# JacdacNRF52833HighPower_32.net
KiCad netlist of a schematic drawn in Altium Designer
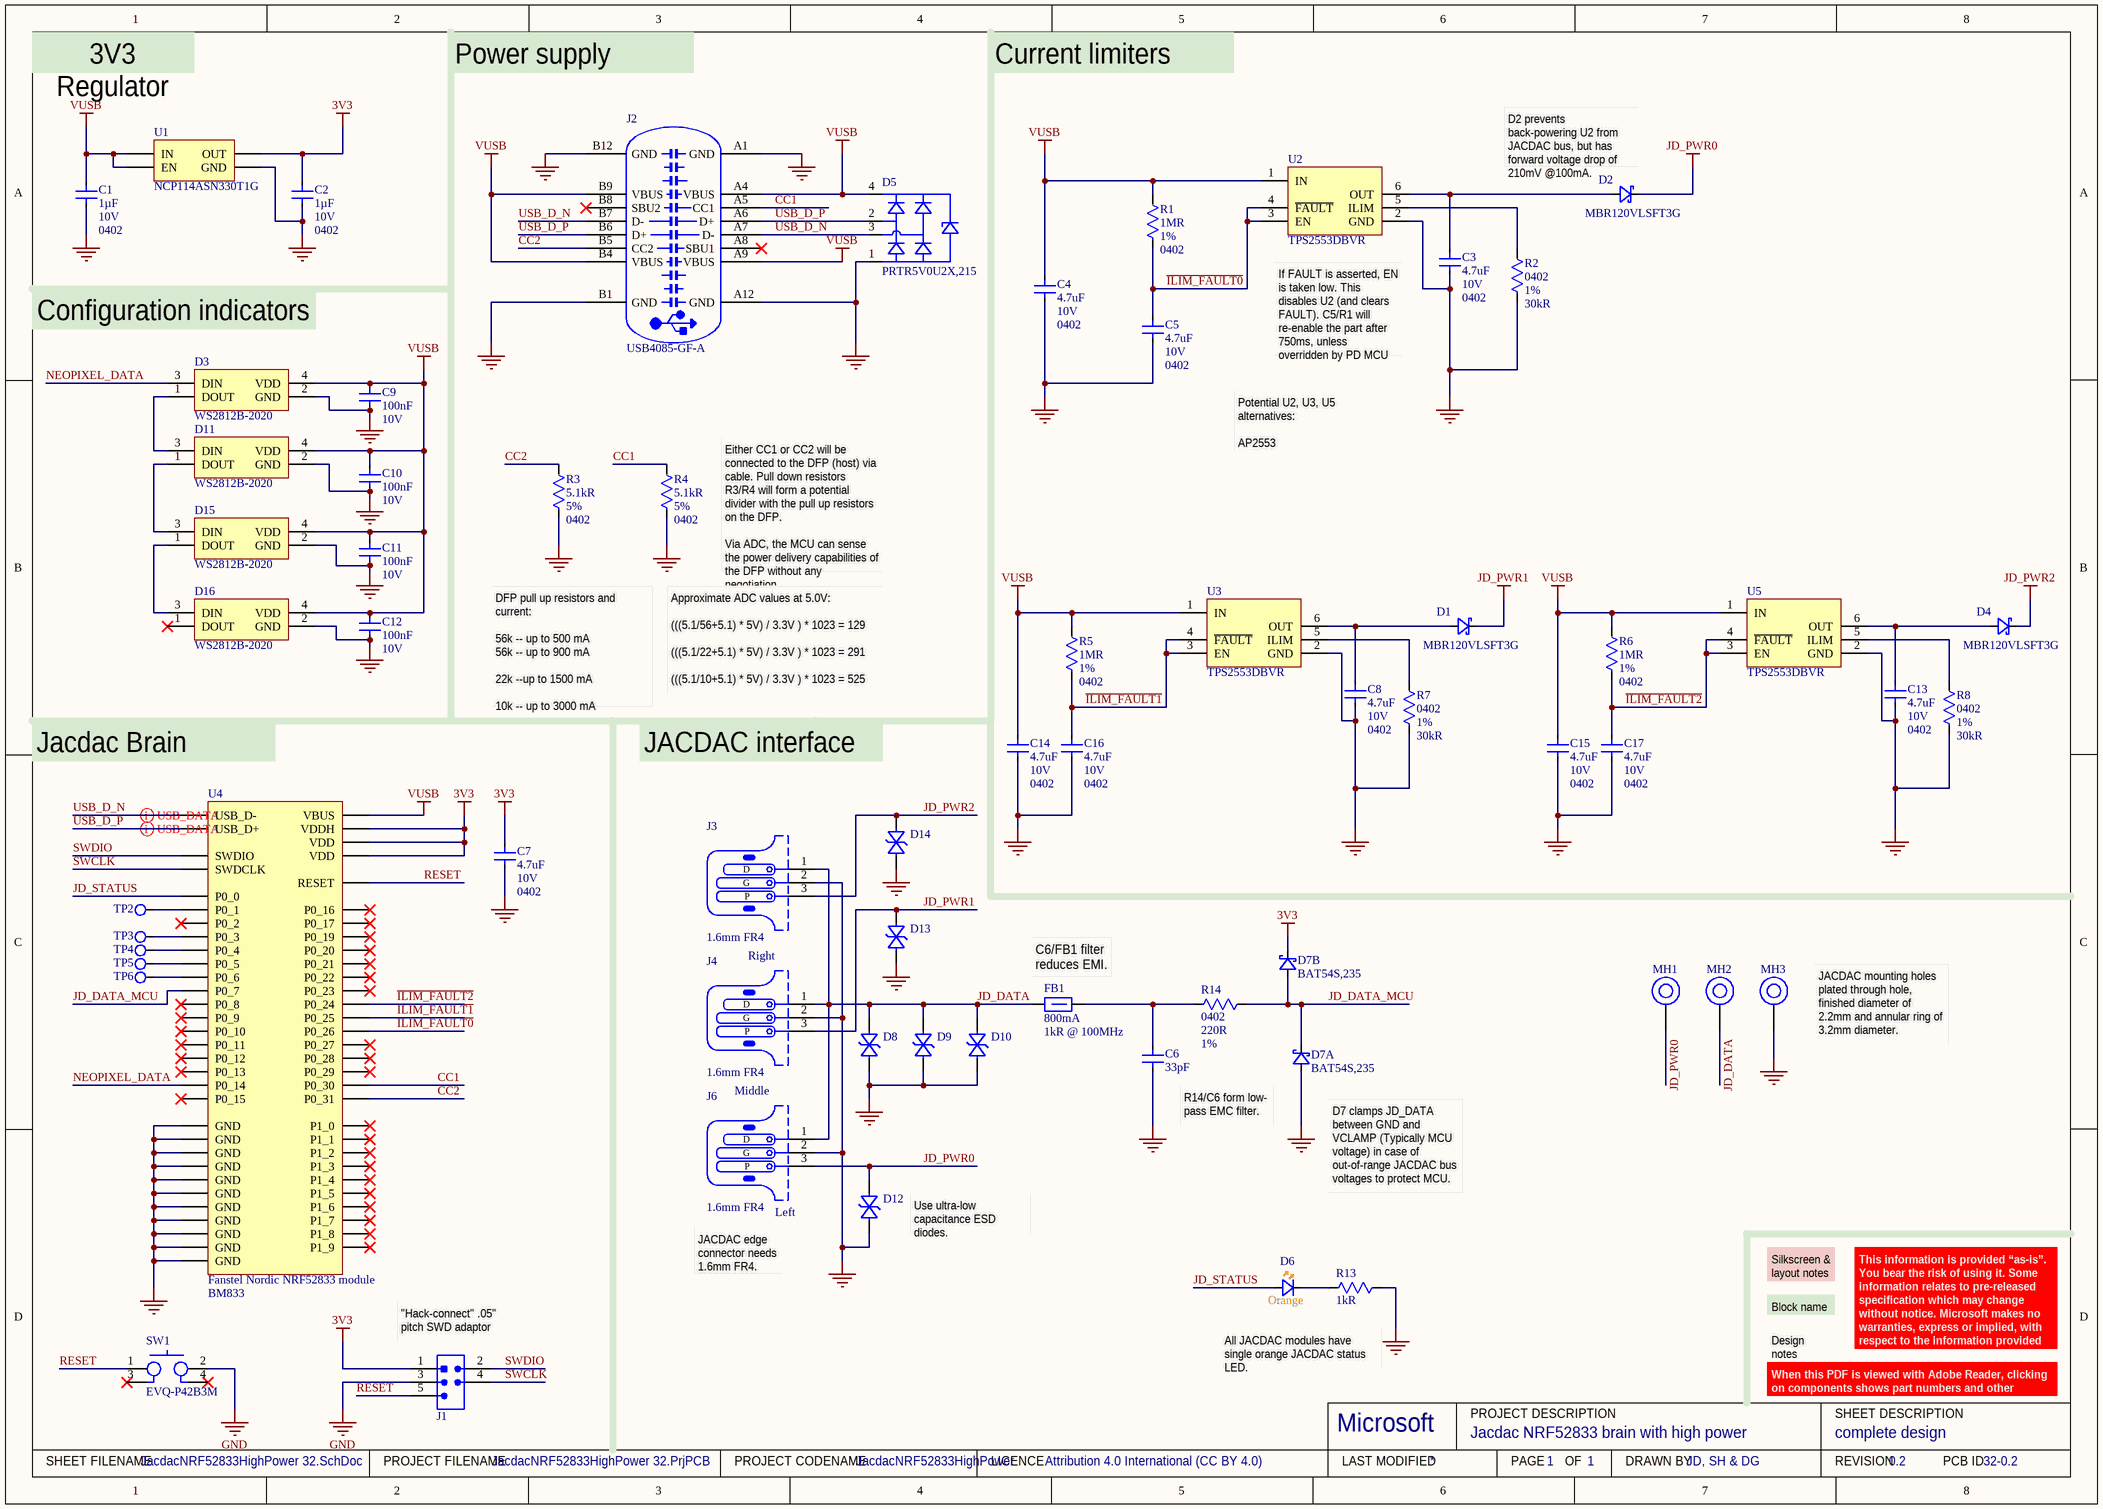
[diagram p0: JacdacNRF52833HighPower 32.SchDoc]

(export (version "E")
  (design (tool "Eeschema 10.0.6"))
  (components
    (comp (ref "C1")
      (value "CL05A105KP5NNNC")
      (footprint "C0402_0.55MM - without outline")
      (description "CAP CER 1UF 10V X5R 0402")
      (fields
        (field (name "MANUFACTURER") "Samsung")
        (field (name "TOLERANCE") "10%")
        (field (name "CAPACITANCE") "1µF")
        (field (name "VOLTAGE RATING") "10V")
        (field (name "CASE CODE (IMPERIAL)") "0402")
        (field (name "CREATED") "DG")
        (field (name "CHECKED") "?")
      )
      (libsource (lib "Samsung") (part "CL05A105KP5NNNC"))
    )
    (comp (ref "C2")
      (value "CL05A105KP5NNNC")
      (footprint "C0402_0.55MM - without outline")
      (description "CAP CER 1UF 10V X5R 0402")
      (fields
        (field (name "MANUFACTURER") "Samsung")
        (field (name "TOLERANCE") "10%")
        (field (name "CAPACITANCE") "1µF")
        (field (name "VOLTAGE RATING") "10V")
        (field (name "CASE CODE (IMPERIAL)") "0402")
        (field (name "CREATED") "DG")
        (field (name "CHECKED") "?")
      )
      (libsource (lib "Samsung") (part "CL05A105KP5NNNC"))
    )
    (comp (ref "C3")
      (value "CL05A475MP5NRNC")
      (footprint "R0402 - Without outline")
      (description "CAP CER 4.7UF 10V X5R 0402")
      (fields
        (field (name "MANUFACTURER") "Samsung")
        (field (name "TOLERANCE") "20%")
        (field (name "CAPACITANCE") "4.7uF")
        (field (name "VOLTAGE RATING") "10V")
        (field (name "CASE CODE (IMPERIAL)") "0402")
        (field (name "CREATED BY") "D. Gakure")
        (field (name "CHECKED BY") "?")
      )
      (libsource (lib "Samsung") (part "CL05A475MP5NRNC"))
    )
    (comp (ref "C4")
      (value "CL05A475MP5NRNC")
      (footprint "R0402 - Without outline")
      (description "CAP CER 4.7UF 10V X5R 0402")
      (fields
        (field (name "MANUFACTURER") "Samsung")
        (field (name "TOLERANCE") "20%")
        (field (name "CAPACITANCE") "4.7uF")
        (field (name "VOLTAGE RATING") "10V")
        (field (name "CASE CODE (IMPERIAL)") "0402")
        (field (name "CREATED BY") "D. Gakure")
        (field (name "CHECKED BY") "?")
      )
      (libsource (lib "Samsung") (part "CL05A475MP5NRNC"))
    )
    (comp (ref "C5")
      (value "CL05A475MP5NRNC")
      (footprint "R0402 - Without outline")
      (description "CAP CER 4.7UF 10V X5R 0402")
      (fields
        (field (name "MANUFACTURER") "Samsung")
        (field (name "TOLERANCE") "20%")
        (field (name "CAPACITANCE") "4.7uF")
        (field (name "VOLTAGE RATING") "10V")
        (field (name "CASE CODE (IMPERIAL)") "0402")
        (field (name "CREATED BY") "D. Gakure")
        (field (name "CHECKED BY") "?")
      )
      (libsource (lib "Samsung") (part "CL05A475MP5NRNC"))
    )
    (comp (ref "C6")
      (value "CL05C330JB51PNC")
      (footprint "C0402_0.55MM - without outline")
      (description "CAP CER 33PF 50V NP0 0402")
      (fields
        (field (name "MANUFACTURER") "Samsung")
        (field (name "TOLERANCE") "5%")
        (field (name "CAPACITANCE") "33pF")
        (field (name "CHECKED") "?")
        (field (name "CREATED") "DG")
      )
      (libsource (lib "Samsung") (part "CL05C330JB51PNC"))
    )
    (comp (ref "C7")
      (value "CL05A475MP5NRNC")
      (footprint "R0402 - Without outline")
      (description "CAP CER 4.7UF 10V X5R 0402")
      (fields
        (field (name "MANUFACTURER") "Samsung")
        (field (name "TOLERANCE") "20%")
        (field (name "CAPACITANCE") "4.7uF")
        (field (name "VOLTAGE RATING") "10V")
        (field (name "CASE CODE (IMPERIAL)") "0402")
        (field (name "CREATED BY") "D. Gakure")
        (field (name "CHECKED BY") "?")
      )
      (libsource (lib "Samsung") (part "CL05A475MP5NRNC"))
    )
    (comp (ref "C8")
      (value "CL05A475MP5NRNC")
      (footprint "R0402 - Without outline")
      (description "CAP CER 4.7UF 10V X5R 0402")
      (fields
        (field (name "MANUFACTURER") "Samsung")
        (field (name "TOLERANCE") "20%")
        (field (name "CAPACITANCE") "4.7uF")
        (field (name "VOLTAGE RATING") "10V")
        (field (name "CASE CODE (IMPERIAL)") "0402")
        (field (name "CREATED BY") "D. Gakure")
        (field (name "CHECKED BY") "?")
      )
      (libsource (lib "Samsung") (part "CL05A475MP5NRNC"))
    )
    (comp (ref "C9")
      (value "CL05B104KP5NNNC")
      (footprint "C0402_0.55MM - without outline")
      (description "CAP CER 0.1UF 10V X7R 0402")
      (fields
        (field (name "MANUFACTURER") "Samsung")
        (field (name "CAPACITANCE") "100nF")
        (field (name "TOLERANCE") "10%")
        (field (name "VOLTAGE RATING") "10V")
        (field (name "CREATED") "DG")
        (field (name "CHECKED") "?")
      )
      (libsource (lib "Samsung") (part "CL05B104KP5NNNC"))
    )
    (comp (ref "C10")
      (value "CL05B104KP5NNNC")
      (footprint "C0402_0.55MM - without outline")
      (description "CAP CER 0.1UF 10V X7R 0402")
      (fields
        (field (name "MANUFACTURER") "Samsung")
        (field (name "CAPACITANCE") "100nF")
        (field (name "TOLERANCE") "10%")
        (field (name "VOLTAGE RATING") "10V")
        (field (name "CREATED") "DG")
        (field (name "CHECKED") "?")
      )
      (libsource (lib "Samsung") (part "CL05B104KP5NNNC"))
    )
    (comp (ref "C11")
      (value "CL05B104KP5NNNC")
      (footprint "C0402_0.55MM - without outline")
      (description "CAP CER 0.1UF 10V X7R 0402")
      (fields
        (field (name "MANUFACTURER") "Samsung")
        (field (name "CAPACITANCE") "100nF")
        (field (name "TOLERANCE") "10%")
        (field (name "VOLTAGE RATING") "10V")
        (field (name "CREATED") "DG")
        (field (name "CHECKED") "?")
      )
      (libsource (lib "Samsung") (part "CL05B104KP5NNNC"))
    )
    (comp (ref "C12")
      (value "CL05B104KP5NNNC")
      (footprint "C0402_0.55MM - without outline")
      (description "CAP CER 0.1UF 10V X7R 0402")
      (fields
        (field (name "MANUFACTURER") "Samsung")
        (field (name "CAPACITANCE") "100nF")
        (field (name "TOLERANCE") "10%")
        (field (name "VOLTAGE RATING") "10V")
        (field (name "CREATED") "DG")
        (field (name "CHECKED") "?")
      )
      (libsource (lib "Samsung") (part "CL05B104KP5NNNC"))
    )
    (comp (ref "C13")
      (value "CL05A475MP5NRNC")
      (footprint "R0402 - Without outline")
      (description "CAP CER 4.7UF 10V X5R 0402")
      (fields
        (field (name "MANUFACTURER") "Samsung")
        (field (name "TOLERANCE") "20%")
        (field (name "CAPACITANCE") "4.7uF")
        (field (name "VOLTAGE RATING") "10V")
        (field (name "CASE CODE (IMPERIAL)") "0402")
        (field (name "CREATED BY") "D. Gakure")
        (field (name "CHECKED BY") "?")
      )
      (libsource (lib "Samsung") (part "CL05A475MP5NRNC"))
    )
    (comp (ref "C14")
      (value "CL05A475MP5NRNC")
      (footprint "R0402 - Without outline")
      (description "CAP CER 4.7UF 10V X5R 0402")
      (fields
        (field (name "MANUFACTURER") "Samsung")
        (field (name "TOLERANCE") "20%")
        (field (name "CAPACITANCE") "4.7uF")
        (field (name "VOLTAGE RATING") "10V")
        (field (name "CASE CODE (IMPERIAL)") "0402")
        (field (name "CREATED BY") "D. Gakure")
        (field (name "CHECKED BY") "?")
      )
      (libsource (lib "Samsung") (part "CL05A475MP5NRNC"))
    )
    (comp (ref "C15")
      (value "CL05A475MP5NRNC")
      (footprint "R0402 - Without outline")
      (description "CAP CER 4.7UF 10V X5R 0402")
      (fields
        (field (name "MANUFACTURER") "Samsung")
        (field (name "TOLERANCE") "20%")
        (field (name "CAPACITANCE") "4.7uF")
        (field (name "VOLTAGE RATING") "10V")
        (field (name "CASE CODE (IMPERIAL)") "0402")
        (field (name "CREATED BY") "D. Gakure")
        (field (name "CHECKED BY") "?")
      )
      (libsource (lib "Samsung") (part "CL05A475MP5NRNC"))
    )
    (comp (ref "C16")
      (value "CL05A475MP5NRNC")
      (footprint "R0402 - Without outline")
      (description "CAP CER 4.7UF 10V X5R 0402")
      (fields
        (field (name "MANUFACTURER") "Samsung")
        (field (name "TOLERANCE") "20%")
        (field (name "CAPACITANCE") "4.7uF")
        (field (name "VOLTAGE RATING") "10V")
        (field (name "CASE CODE (IMPERIAL)") "0402")
        (field (name "CREATED BY") "D. Gakure")
        (field (name "CHECKED BY") "?")
      )
      (libsource (lib "Samsung") (part "CL05A475MP5NRNC"))
    )
    (comp (ref "C17")
      (value "CL05A475MP5NRNC")
      (footprint "R0402 - Without outline")
      (description "CAP CER 4.7UF 10V X5R 0402")
      (fields
        (field (name "MANUFACTURER") "Samsung")
        (field (name "TOLERANCE") "20%")
        (field (name "CAPACITANCE") "4.7uF")
        (field (name "VOLTAGE RATING") "10V")
        (field (name "CASE CODE (IMPERIAL)") "0402")
        (field (name "CREATED BY") "D. Gakure")
        (field (name "CHECKED BY") "?")
      )
      (libsource (lib "Samsung") (part "CL05A475MP5NRNC"))
    )
    (comp (ref "D1")
      (value "MBR120VLSFT3G")
      (footprint "MBR120VLSFT3G")
      (description "DIODE SCHOTTKY 20V 1A SOD123FL")
      (fields
        (field (name "MANUFACTURER") "ON Semiconductor")
        (field (name "MANUFACTURER PART NUMBER") "MBR120VLSFT3G")
      )
      (libsource (lib "OnSemiconductor") (part "MBR120VLSFT3G"))
    )
    (comp (ref "D2")
      (value "MBR120VLSFT3G")
      (footprint "MBR120VLSFT3G")
      (description "DIODE SCHOTTKY 20V 1A SOD123FL")
      (fields
        (field (name "MANUFACTURER") "ON Semiconductor")
        (field (name "MANUFACTURER PART NUMBER") "MBR120VLSFT3G")
      )
      (libsource (lib "OnSemiconductor") (part "MBR120VLSFT3G"))
    )
    (comp (ref "D3")
      (value "WS2812B-2020")
      (footprint "WORLDSEMI_WS2812B-2020:WS2812B-2020")
      (description "WS2812B RGB LED (Neopixel) 2.0mm x 2.0mm")
      (fields (field (name "MANUFACTURER PART NUMBER") "WS2812B-2020"))
      (libsource (lib "WorldSemi") (part "WS2812B-2020"))
    )
    (comp (ref "D4")
      (value "MBR120VLSFT3G")
      (footprint "MBR120VLSFT3G")
      (description "DIODE SCHOTTKY 20V 1A SOD123FL")
      (fields
        (field (name "MANUFACTURER") "ON Semiconductor")
        (field (name "MANUFACTURER PART NUMBER") "MBR120VLSFT3G")
      )
      (libsource (lib "OnSemiconductor") (part "MBR120VLSFT3G"))
    )
    (comp (ref "D5")
      (value "NXP-PRTR5V0U2X,215-4-whitesch")
      (footprint "NXP-SOT143B-4_V")
      (description "USB TVS and ESD protection diodes")
      (fields
        (field (name "MANUFACTURER") "NXP Semiconductors")
        (field (name "MANUFACTURER PART NUMBER") "PRTR5V0U2X,215")
      )
      (libsource (lib "NXP") (part "NXP-PRTR5V0U2X,215-4-whitesch"))
    )
    (comp (ref "D6")
      (value "Right angle mount LED (orange)")
      (footprint "LITE-ON_LTST-S220KFKT:LTST-S220KFKT")
      (description "LED ORANGE CLEAR SMD R/A")
      (libsource (lib "Lite-On") (part "LTST-S220KFKT"))
    )
    (comp (ref "D7")
      (value "BAT54S")
      (footprint "NXP-BAT54S-TO-236AB")
      (description "DIODE ARRAY SCHOTTKY 30V SOT23")
      (fields (field (name "MANUFACTURER") "Nexperia") (field (name "MANUFACTURER PART NUMBER") "BAT54S,235"))
      (libsource (lib "NXP") (part "BAT54S"))
    )
    (comp (ref "D8")
      (value "VBUS05B1-SD0-G4-08")
      (footprint "0201-VBUS05B1-SD0-G4-08 - Without outline")
      (description "TVS DIODE 5.5V 18V CLP0603")
      (fields
        (field (name "MANUFACTURER") "Vishay Semiconductors")
        (field (name "CREATED BY") "D. Gakure")
        (field (name "CHECKED BY") "?")
      )
      (libsource (lib "Vishay") (part "VBUS05B1-SD0-G4-08"))
    )
    (comp (ref "D9")
      (value "VBUS05B1-SD0-G4-08")
      (footprint "0201-VBUS05B1-SD0-G4-08 - Without outline")
      (description "TVS DIODE 5.5V 18V CLP0603")
      (fields
        (field (name "MANUFACTURER") "Vishay Semiconductors")
        (field (name "CREATED BY") "D. Gakure")
        (field (name "CHECKED BY") "?")
      )
      (libsource (lib "Vishay") (part "VBUS05B1-SD0-G4-08"))
    )
    (comp (ref "D10")
      (value "VBUS05B1-SD0-G4-08")
      (footprint "0201-VBUS05B1-SD0-G4-08 - Without outline")
      (description "TVS DIODE 5.5V 18V CLP0603")
      (fields
        (field (name "MANUFACTURER") "Vishay Semiconductors")
        (field (name "CREATED BY") "D. Gakure")
        (field (name "CHECKED BY") "?")
      )
      (libsource (lib "Vishay") (part "VBUS05B1-SD0-G4-08"))
    )
    (comp (ref "D11")
      (value "WS2812B-2020")
      (footprint "WORLDSEMI_WS2812B-2020:WS2812B-2020")
      (description "WS2812B RGB LED (Neopixel) 2.0mm x 2.0mm")
      (fields (field (name "MANUFACTURER PART NUMBER") "WS2812B-2020"))
      (libsource (lib "WorldSemi") (part "WS2812B-2020"))
    )
    (comp (ref "D12")
      (value "VBUS05B1-SD0-G4-08")
      (footprint "0201-VBUS05B1-SD0-G4-08 - Without outline")
      (description "TVS DIODE 5.5V 18V CLP0603")
      (fields
        (field (name "MANUFACTURER") "Vishay Semiconductors")
        (field (name "CREATED BY") "D. Gakure")
        (field (name "CHECKED BY") "?")
      )
      (libsource (lib "Vishay") (part "VBUS05B1-SD0-G4-08"))
    )
    (comp (ref "D13")
      (value "VBUS05B1-SD0-G4-08")
      (footprint "0201-VBUS05B1-SD0-G4-08 - Without outline")
      (description "TVS DIODE 5.5V 18V CLP0603")
      (fields
        (field (name "MANUFACTURER") "Vishay Semiconductors")
        (field (name "CREATED BY") "D. Gakure")
        (field (name "CHECKED BY") "?")
      )
      (libsource (lib "Vishay") (part "VBUS05B1-SD0-G4-08"))
    )
    (comp (ref "D14")
      (value "VBUS05B1-SD0-G4-08")
      (footprint "0201-VBUS05B1-SD0-G4-08 - Without outline")
      (description "TVS DIODE 5.5V 18V CLP0603")
      (fields
        (field (name "MANUFACTURER") "Vishay Semiconductors")
        (field (name "CREATED BY") "D. Gakure")
        (field (name "CHECKED BY") "?")
      )
      (libsource (lib "Vishay") (part "VBUS05B1-SD0-G4-08"))
    )
    (comp (ref "D15")
      (value "WS2812B-2020")
      (footprint "WORLDSEMI_WS2812B-2020:WS2812B-2020")
      (description "WS2812B RGB LED (Neopixel) 2.0mm x 2.0mm")
      (fields (field (name "MANUFACTURER PART NUMBER") "WS2812B-2020"))
      (libsource (lib "WorldSemi") (part "WS2812B-2020"))
    )
    (comp (ref "D16")
      (value "WS2812B-2020")
      (footprint "WORLDSEMI_WS2812B-2020:WS2812B-2020")
      (description "WS2812B RGB LED (Neopixel) 2.0mm x 2.0mm")
      (fields (field (name "MANUFACTURER PART NUMBER") "WS2812B-2020"))
      (libsource (lib "WorldSemi") (part "WS2812B-2020"))
    )
    (comp (ref "FB1")
      (value "TDK MPZ1608S102ATA00")
      (footprint "TDK MPZ1608 0.8mm - without outline")
      (description "0603 1k@100MHz 0.8A chip")
      (fields
        (field (name "TOLERANCE") "25%")
        (field (name "MANUFACTURER") "TDK")
        (field (name "CURRENT RATING") "800mA")
        (field (name "IMPEDANCE") "1kR @ 100MHz")
      )
      (libsource (lib "TDK") (part "TDK MPZ1608S102ATA00"))
    )
    (comp (ref "J1")
      (value "Hack Connect Mini 1.27 mm pitch 2-row")
      (footprint "HACK_CONNECT_MINI_5_X_1_27")
      (libsource (lib "generic-con") (part "HACK_CONNECT_MINI"))
    )
    (comp (ref "J2")
      (value "USB4085-GF-A")
      (footprint "GCT_USB4085-GF-A:USB4085-GF-A")
      (description "USB4085 Series 20 V PCB Top Mount USB 2.0 Type C Receptacle")
      (fields (field (name "MANUFACTURER PART NUMBER 1") "USB4085-GF-A"))
      (libsource (lib "GCT") (part "USB4085-GF-A"))
    )
    (comp (ref "J3")
      (value "JACDAC edge connector")
      (footprint "JACDAC_edge_connector:JACDAC_EDGE_CONNECTOR_0.2mm_T&G")
      (description "3 pin jacdac edge connector 1.27mm pitch")
      (fields
        (field (name "MANUFACTURER PART NUMBER") "JACDAC_EDGE_CONNECTOR")
        (field (name "PCB TYPE") "1.6mm FR4")
        (field (name "CHECKED BY") "?")
        (field (name "CREATED BY") "D. Gakure")
      )
      (libsource (lib "generic-con") (part "Jacdac edge connector"))
    )
    (comp (ref "J4")
      (value "JACDAC edge connector")
      (footprint "JACDAC_edge_connector:JACDAC_EDGE_CONNECTOR_0.2mm_T&G")
      (description "3 pin jacdac edge connector 1.27mm pitch")
      (fields
        (field (name "MANUFACTURER PART NUMBER") "JACDAC_EDGE_CONNECTOR")
        (field (name "PCB TYPE") "1.6mm FR4")
        (field (name "CHECKED BY") "?")
        (field (name "CREATED BY") "D. Gakure")
      )
      (libsource (lib "generic-con") (part "Jacdac edge connector"))
    )
    (comp (ref "J6")
      (value "JACDAC edge connector")
      (footprint "JACDAC_edge_connector:JACDAC_EDGE_CONNECTOR_0.2mm_T&G")
      (description "3 pin jacdac edge connector 1.27mm pitch")
      (fields
        (field (name "MANUFACTURER PART NUMBER") "JACDAC_EDGE_CONNECTOR")
        (field (name "PCB TYPE") "1.6mm FR4")
        (field (name "CHECKED BY") "?")
        (field (name "CREATED BY") "D. Gakure")
      )
      (libsource (lib "generic-con") (part "Jacdac edge connector"))
    )
    (comp (ref "MH1")
      (value "MH_5.0MMK_3.0MMC_2.1MMD_PTH")
      (footprint "MH_5.0MMK_3.0MMC_2.1MMD_PTH")
      (description "Mounting Hole 5.0mm keepout, 3.0mm annualar ring and 2.1mm Drill PTH")
      (libsource (lib "generic") (part "MH_5.0MMK_3.0MMC_2.1MMD_PTH"))
    )
    (comp (ref "MH2")
      (value "MH_5.0MMK_3.0MMC_2.1MMD_PTH")
      (footprint "MH_5.0MMK_3.0MMC_2.1MMD_PTH")
      (description "Mounting Hole 5.0mm keepout, 3.0mm annualar ring and 2.1mm Drill PTH")
      (libsource (lib "generic") (part "MH_5.0MMK_3.0MMC_2.1MMD_PTH"))
    )
    (comp (ref "MH3")
      (value "MH_5.0MMK_3.0MMC_2.1MMD_PTH")
      (footprint "MH_5.0MMK_3.0MMC_2.1MMD_PTH")
      (description "Mounting Hole 5.0mm keepout, 3.0mm annualar ring and 2.1mm Drill PTH")
      (libsource (lib "generic") (part "MH_5.0MMK_3.0MMC_2.1MMD_PTH"))
    )
    (comp (ref "R1")
      (value "~")
      (footprint "R0402 - Without outline")
      (description "RES SMD 1M OHM 1% 1/16W 0402")
      (fields
        (field (name "MANUFACTURER") "Yageo")
        (field (name "MANUFACTURER PART NUMBER") "RC0402FR-071ML")
        (field (name "RESISTANCE") "1MR")
        (field (name "TOLERANCE") "1%")
        (field (name "CASE CODE (IMPERIAL)") "0402")
        (field (name "CREATED BY") "D. Gakure")
        (field (name "CHECKED BY") "?")
      )
      (libsource (lib "Yageo") (part "RC0402FR-071ML"))
    )
    (comp (ref "R2")
      (value "0402 RES SMD 30k 1%")
      (footprint "YAGEO-0402:R0402")
      (description "YAGEO - RC0402FR-0730KL - RES, 30K, 1%, 0.063W, 0402, THICK FILM")
      (fields
        (field (name "CASE/PACKAGE") "0402")
        (field (name "TOLERANCE") "1%")
        (field (name "RESISTANCE") "30kR")
      )
      (libsource (lib "Yageo") (part "RC0402FR-0730KL"))
    )
    (comp (ref "R3")
      (value "RC0402JR-075K1L")
      (footprint "R0402 - Without outline")
      (description "RES SMD 5.1K OHM 5% 1/16W 0402")
      (fields
        (field (name "MANUFACTURER") "Yageo")
        (field (name "RESISTANCE") "5.1kR")
        (field (name "TOLERANCE") "5%")
        (field (name "CASE CODE (IMPERIAL)") "0402")
        (field (name "CREATED BY") "D. Gakure")
        (field (name "CHECKED BY") "?")
      )
      (libsource (lib "Yageo") (part "RC0402JR-075K1L"))
    )
    (comp (ref "R4")
      (value "RC0402JR-075K1L")
      (footprint "R0402 - Without outline")
      (description "RES SMD 5.1K OHM 5% 1/16W 0402")
      (fields
        (field (name "MANUFACTURER") "Yageo")
        (field (name "RESISTANCE") "5.1kR")
        (field (name "TOLERANCE") "5%")
        (field (name "CASE CODE (IMPERIAL)") "0402")
        (field (name "CREATED BY") "D. Gakure")
        (field (name "CHECKED BY") "?")
      )
      (libsource (lib "Yageo") (part "RC0402JR-075K1L"))
    )
    (comp (ref "R5")
      (value "~")
      (footprint "R0402 - Without outline")
      (description "RES SMD 1M OHM 1% 1/16W 0402")
      (fields
        (field (name "MANUFACTURER") "Yageo")
        (field (name "MANUFACTURER PART NUMBER") "RC0402FR-071ML")
        (field (name "RESISTANCE") "1MR")
        (field (name "TOLERANCE") "1%")
        (field (name "CASE CODE (IMPERIAL)") "0402")
        (field (name "CREATED BY") "D. Gakure")
        (field (name "CHECKED BY") "?")
      )
      (libsource (lib "Yageo") (part "RC0402FR-071ML"))
    )
    (comp (ref "R6")
      (value "~")
      (footprint "R0402 - Without outline")
      (description "RES SMD 1M OHM 1% 1/16W 0402")
      (fields
        (field (name "MANUFACTURER") "Yageo")
        (field (name "MANUFACTURER PART NUMBER") "RC0402FR-071ML")
        (field (name "RESISTANCE") "1MR")
        (field (name "TOLERANCE") "1%")
        (field (name "CASE CODE (IMPERIAL)") "0402")
        (field (name "CREATED BY") "D. Gakure")
        (field (name "CHECKED BY") "?")
      )
      (libsource (lib "Yageo") (part "RC0402FR-071ML"))
    )
    (comp (ref "R7")
      (value "0402 RES SMD 30k 1%")
      (footprint "YAGEO-0402:R0402")
      (description "YAGEO - RC0402FR-0730KL - RES, 30K, 1%, 0.063W, 0402, THICK FILM")
      (fields
        (field (name "CASE/PACKAGE") "0402")
        (field (name "TOLERANCE") "1%")
        (field (name "RESISTANCE") "30kR")
      )
      (libsource (lib "Yageo") (part "RC0402FR-0730KL"))
    )
    (comp (ref "R8")
      (value "0402 RES SMD 30k 1%")
      (footprint "YAGEO-0402:R0402")
      (description "YAGEO - RC0402FR-0730KL - RES, 30K, 1%, 0.063W, 0402, THICK FILM")
      (fields
        (field (name "CASE/PACKAGE") "0402")
        (field (name "TOLERANCE") "1%")
        (field (name "RESISTANCE") "30kR")
      )
      (libsource (lib "Yageo") (part "RC0402FR-0730KL"))
    )
    (comp (ref "R13")
      (value "RC0402FR-071KL")
      (footprint "R0402 - Without outline")
      (description "RES SMD 1K OHM 1% 1/16W 0402")
      (fields
        (field (name "MANUFACTURER") "Yageo")
        (field (name "TOLERANCE") "1%")
        (field (name "RESISTANCE") "1kR")
        (field (name "CREATED") "D.G")
        (field (name "CHECKED") "?")
      )
      (libsource (lib "Yageo") (part "RC0402FR-071KL"))
    )
    (comp (ref "R14")
      (value "RC0402FR-07220RL")
      (footprint "R0402 - Without outline")
      (description "RES SMD 220 OHM 1% 1/16W 0402")
      (fields
        (field (name "MANUFACTURER") "Yageo")
        (field (name "CASE CODE (IMPERIAL)") "0402")
        (field (name "RESISTANCE") "220R")
        (field (name "TOLERANCE") "1%")
        (field (name "CREATED") "D.G")
        (field (name "CHECKED") "?")
      )
      (libsource (lib "Yageo") (part "RC0402FR-07220RL"))
    )
    (comp (ref "SW1")
      (value "Side mount digital switch.")
      (footprint "PANASONIC-EVQ-P42B3M:EVQ-P42B3M")
      (description "Switch Tactile N.O. SPST Button J-Bend 0.02A 15VDC 1.6N SMD Embossed T/R")
      (fields (field (name "MANUFACTURER PART NUMBER") "EVQ-P42B3M"))
      (libsource (lib "Panasonic") (part "EVQ-P42B3M"))
    )
    (comp (ref "TP2")
      (value "TestPoint")
      (footprint "Pad1.27mm")
      (description "Test Point")
      (libsource (lib "generic") (part "TestPoint"))
    )
    (comp (ref "TP3")
      (value "TestPoint")
      (footprint "Pad1.27mm")
      (description "Test Point")
      (libsource (lib "generic") (part "TestPoint"))
    )
    (comp (ref "TP4")
      (value "TestPoint")
      (footprint "Pad1.27mm")
      (description "Test Point")
      (libsource (lib "generic") (part "TestPoint"))
    )
    (comp (ref "TP5")
      (value "TestPoint")
      (footprint "Pad1.27mm")
      (description "Test Point")
      (libsource (lib "generic") (part "TestPoint"))
    )
    (comp (ref "TP6")
      (value "TestPoint")
      (footprint "Pad1.27mm")
      (description "Test Point")
      (libsource (lib "generic") (part "TestPoint"))
    )
    (comp (ref "U1")
      (value "LDO 3.3V/300 mA")
      (footprint "ON_SEMI-SOT23-5")
      (fields
        (field (name "MANUFACTURER") "ON Semiconductor")
        (field (name "MANUFACTURER PART NUMBER") "NCP114ASN330T1G")
        (field (name "CREATED") "DG")
        (field (name "CHECKED") "?")
      )
      (libsource (lib "OnSemiconductor") (part "NCP114ASN330T1G"))
    )
    (comp (ref "U2")
      (value "TPS2553DBVR_ALT")
      (footprint "TI-TPS2553")
      (fields (field (name "MANUFACTURER PART NUMBER 1") "TPS2553DBVR"))
      (libsource (lib "TexasInstruments") (part "TPS2553DBVR_ALT"))
    )
    (comp (ref "U3")
      (value "TPS2553DBVR_ALT")
      (footprint "TI-TPS2553")
      (fields (field (name "MANUFACTURER PART NUMBER 1") "TPS2553DBVR"))
      (libsource (lib "TexasInstruments") (part "TPS2553DBVR_ALT"))
    )
    (comp (ref "U4")
      (value "Fanstel Nordic NRF52833 module")
      (footprint "FANSTEL_BM833:BM833")
      (description "Fanstel Nordic nRF52833 module")
      (fields (field (name "MANUFACTURER PART NUMBER 1") "BM833"))
      (libsource (lib "Fanstel") (part "BM833"))
    )
    (comp (ref "U5")
      (value "TPS2553DBVR_ALT")
      (footprint "TI-TPS2553")
      (fields (field (name "MANUFACTURER PART NUMBER 1") "TPS2553DBVR"))
      (libsource (lib "TexasInstruments") (part "TPS2553DBVR_ALT"))
    )
  )
  (nets
    (net (code "1") (name "/CC1") (class "Default")
      (node (ref "J2") (pin "A5") (pinfunction "CC1_A5") (pintype "passive"))
      (node (ref "R4") (pin "1") (pinfunction "1_1") (pintype "passive"))
      (node (ref "U4") (pin "11") (pinfunction "P0_30_11") (pintype "passive"))
    )
    (net (code "2") (name "/CC2") (class "Default")
      (node (ref "J2") (pin "B5") (pinfunction "CC2_B5") (pintype "passive"))
      (node (ref "R3") (pin "1") (pinfunction "1_1") (pintype "passive"))
      (node (ref "U4") (pin "12") (pinfunction "P0_31_12") (pintype "passive"))
    )
    (net (code "3") (name "/JD_DATA") (class "Default")
      (node (ref "D10") (pin "1") (pinfunction "K_1") (pintype "passive"))
      (node (ref "D8") (pin "1") (pinfunction "K_1") (pintype "passive"))
      (node (ref "D9") (pin "1") (pinfunction "K_1") (pintype "passive"))
      (node (ref "FB1") (pin "1") (pinfunction "1_1") (pintype "passive"))
      (node (ref "J3") (pin "1") (pinfunction "D_1") (pintype "passive"))
      (node (ref "J4") (pin "1") (pinfunction "D_1") (pintype "passive"))
      (node (ref "J6") (pin "1") (pinfunction "D_1") (pintype "passive"))
      (node (ref "MH2") (pin "1") (pinfunction "1_1") (pintype "passive"))
    )
    (net (code "4") (name "/JD_DATA_MCU") (class "Default")
      (node (ref "D7") (pin "3") (pinfunction "K_3") (pintype "passive"))
      (node (ref "R14") (pin "1") (pinfunction "1_1") (pintype "passive"))
      (node (ref "U4") (pin "24") (pinfunction "P0_7_24") (pintype "passive"))
    )
    (net (code "5") (name "/JD_STATUS") (class "Default")
      (node (ref "D6") (pin "2") (pinfunction "A_2") (pintype "passive"))
      (node (ref "U4") (pin "16") (pinfunction "P0_0_16") (pintype "passive"))
    )
    (net (code "6") (name "/NEOPIXEL_DATA") (class "Default")
      (node (ref "D3") (pin "3") (pinfunction "DIN_3") (pintype "passive"))
      (node (ref "U4") (pin "33") (pinfunction "P0_14_33") (pintype "passive"))
    )
    (net (code "7") (name "/RESET") (class "Default")
      (node (ref "J1") (pin "5") (pinfunction "RESET_5") (pintype "passive"))
      (node (ref "SW1") (pin "1") (pinfunction "A_1") (pintype "passive"))
      (node (ref "U4") (pin "40") (pinfunction "RESET_40") (pintype "passive"))
    )
    (net (code "8") (name "/SWCLK") (class "Default")
      (node (ref "J1") (pin "4") (pinfunction "SWCLK_4") (pintype "passive"))
      (node (ref "U4") (pin "42") (pinfunction "SWDCLK_42") (pintype "passive"))
    )
    (net (code "9") (name "/SWDIO") (class "Default")
      (node (ref "J1") (pin "2") (pinfunction "SWDIO_2") (pintype "passive"))
      (node (ref "U4") (pin "43") (pinfunction "SWDIO_43") (pintype "passive"))
    )
    (net (code "10") (name "/USB_D_N") (class "Default")
      (node (ref "D5") (pin "3") (pinfunction "I/O2_3") (pintype "passive"))
      (node (ref "J2") (pin "A7") (pinfunction "D-_A7") (pintype "passive"))
      (node (ref "J2") (pin "B7") (pinfunction "D-_B7") (pintype "passive"))
      (node (ref "U4") (pin "68") (pinfunction "USB_D-_68") (pintype "passive"))
    )
    (net (code "11") (name "/USB_D_P") (class "Default")
      (node (ref "D5") (pin "2") (pinfunction "I/O1_2") (pintype "passive"))
      (node (ref "J2") (pin "A6") (pinfunction "D+_A6") (pintype "passive"))
      (node (ref "J2") (pin "B6") (pinfunction "D+_B6") (pintype "passive"))
      (node (ref "U4") (pin "67") (pinfunction "USB_D+_67") (pintype "passive"))
    )
    (net (code "12") (name "/~{ILIM_FAULT0}") (class "Default")
      (node (ref "C5") (pin "2") (pinfunction "2_2") (pintype "passive"))
      (node (ref "R1") (pin "2") (pinfunction "2_2") (pintype "passive"))
      (node (ref "U2") (pin "3") (pinfunction "EN_3") (pintype "passive"))
      (node (ref "U2") (pin "4") (pinfunction "~{FAULT}_4") (pintype "passive"))
      (node (ref "U4") (pin "7") (pinfunction "P0_26_7") (pintype "passive"))
    )
    (net (code "13") (name "/~{ILIM_FAULT1}") (class "Default")
      (node (ref "C16") (pin "2") (pinfunction "2_2") (pintype "passive"))
      (node (ref "R5") (pin "2") (pinfunction "2_2") (pintype "passive"))
      (node (ref "U3") (pin "3") (pinfunction "EN_3") (pintype "passive"))
      (node (ref "U3") (pin "4") (pinfunction "~{FAULT}_4") (pintype "passive"))
      (node (ref "U4") (pin "55") (pinfunction "P0_25_55") (pintype "passive"))
    )
    (net (code "14") (name "/~{ILIM_FAULT2}") (class "Default")
      (node (ref "C17") (pin "2") (pinfunction "2_2") (pintype "passive"))
      (node (ref "R6") (pin "2") (pinfunction "2_2") (pintype "passive"))
      (node (ref "U4") (pin "47") (pinfunction "P0_24_47") (pintype "passive"))
      (node (ref "U5") (pin "3") (pinfunction "EN_3") (pintype "passive"))
      (node (ref "U5") (pin "4") (pinfunction "~{FAULT}_4") (pintype "passive"))
    )
    (net (code "15") (name "3V3") (class "Default")
      (node (ref "C2") (pin "2") (pinfunction "2_2") (pintype "passive"))
      (node (ref "C7") (pin "2") (pinfunction "2_2") (pintype "passive"))
      (node (ref "D7") (pin "2") (pinfunction "K_2") (pintype "passive"))
      (node (ref "J1") (pin "1") (pinfunction "VCC_1") (pintype "passive"))
      (node (ref "U1") (pin "5") (pinfunction "OUT_5") (pintype "passive"))
      (node (ref "U4") (pin "14") (pinfunction "VDD_14") (pintype "passive"))
      (node (ref "U4") (pin "28") (pinfunction "VDD_28") (pintype "passive"))
      (node (ref "U4") (pin "56") (pinfunction "VDDH_56") (pintype "passive"))
    )
    (net (code "16") (name "GND") (class "Default")
      (node (ref "C1") (pin "1") (pinfunction "1_1") (pintype "passive"))
      (node (ref "C10") (pin "1") (pinfunction "1_1") (pintype "passive"))
      (node (ref "C11") (pin "1") (pinfunction "1_1") (pintype "passive"))
      (node (ref "C12") (pin "1") (pinfunction "1_1") (pintype "passive"))
      (node (ref "C13") (pin "1") (pinfunction "1_1") (pintype "passive"))
      (node (ref "C14") (pin "1") (pinfunction "1_1") (pintype "passive"))
      (node (ref "C15") (pin "1") (pinfunction "1_1") (pintype "passive"))
      (node (ref "C16") (pin "1") (pinfunction "1_1") (pintype "passive"))
      (node (ref "C17") (pin "1") (pinfunction "1_1") (pintype "passive"))
      (node (ref "C2") (pin "1") (pinfunction "1_1") (pintype "passive"))
      (node (ref "C3") (pin "1") (pinfunction "1_1") (pintype "passive"))
      (node (ref "C4") (pin "1") (pinfunction "1_1") (pintype "passive"))
      (node (ref "C5") (pin "1") (pinfunction "1_1") (pintype "passive"))
      (node (ref "C6") (pin "1") (pinfunction "1_1") (pintype "passive"))
      (node (ref "C7") (pin "1") (pinfunction "1_1") (pintype "passive"))
      (node (ref "C8") (pin "1") (pinfunction "1_1") (pintype "passive"))
      (node (ref "C9") (pin "1") (pinfunction "1_1") (pintype "passive"))
      (node (ref "D10") (pin "2") (pinfunction "A_2") (pintype "passive"))
      (node (ref "D11") (pin "2") (pinfunction "GND_2") (pintype "passive"))
      (node (ref "D12") (pin "2") (pinfunction "A_2") (pintype "passive"))
      (node (ref "D13") (pin "2") (pinfunction "A_2") (pintype "passive"))
      (node (ref "D14") (pin "2") (pinfunction "A_2") (pintype "passive"))
      (node (ref "D15") (pin "2") (pinfunction "GND_2") (pintype "passive"))
      (node (ref "D16") (pin "2") (pinfunction "GND_2") (pintype "passive"))
      (node (ref "D3") (pin "2") (pinfunction "GND_2") (pintype "passive"))
      (node (ref "D5") (pin "1") (pinfunction "GND_1") (pintype "power_in"))
      (node (ref "D7") (pin "1") (pinfunction "A_1") (pintype "passive"))
      (node (ref "D8") (pin "2") (pinfunction "A_2") (pintype "passive"))
      (node (ref "D9") (pin "2") (pinfunction "A_2") (pintype "passive"))
      (node (ref "J1") (pin "3") (pinfunction "GND_3") (pintype "passive"))
      (node (ref "J2") (pin "A1") (pinfunction "GND_A1") (pintype "passive"))
      (node (ref "J2") (pin "A12") (pinfunction "GND_A12") (pintype "passive"))
      (node (ref "J2") (pin "B1") (pinfunction "GND_B1") (pintype "passive"))
      (node (ref "J2") (pin "B12") (pinfunction "GND_B12") (pintype "passive"))
      (node (ref "J3") (pin "2") (pinfunction "G_2") (pintype "passive"))
      (node (ref "J4") (pin "2") (pinfunction "G_2") (pintype "passive"))
      (node (ref "J6") (pin "2") (pinfunction "G_2") (pintype "passive"))
      (node (ref "MH3") (pin "1") (pinfunction "1_1") (pintype "passive"))
      (node (ref "R13") (pin "1") (pinfunction "1_1") (pintype "passive"))
      (node (ref "R2") (pin "1") (pinfunction "1_1") (pintype "passive"))
      (node (ref "R3") (pin "2") (pinfunction "2_2") (pintype "passive"))
      (node (ref "R4") (pin "2") (pinfunction "2_2") (pintype "passive"))
      (node (ref "R7") (pin "1") (pinfunction "1_1") (pintype "passive"))
      (node (ref "R8") (pin "1") (pinfunction "1_1") (pintype "passive"))
      (node (ref "SW1") (pin "2") (pinfunction "B_2") (pintype "passive"))
      (node (ref "U1") (pin "2") (pinfunction "GND_2") (pintype "passive"))
      (node (ref "U2") (pin "2") (pinfunction "GND_2") (pintype "passive"))
      (node (ref "U3") (pin "2") (pinfunction "GND_2") (pintype "passive"))
      (node (ref "U4") (pin "1") (pinfunction "GND_1") (pintype "passive"))
      (node (ref "U4") (pin "13") (pinfunction "GND_13") (pintype "passive"))
      (node (ref "U4") (pin "15") (pinfunction "GND_15") (pintype "passive"))
      (node (ref "U4") (pin "18") (pinfunction "GND_18") (pintype "passive"))
      (node (ref "U4") (pin "19") (pinfunction "GND_19") (pintype "passive"))
      (node (ref "U4") (pin "2") (pinfunction "GND_2") (pintype "passive"))
      (node (ref "U4") (pin "3") (pinfunction "GND_3") (pintype "passive"))
      (node (ref "U4") (pin "30") (pinfunction "GND_30") (pintype "passive"))
      (node (ref "U4") (pin "4") (pinfunction "GND_4") (pintype "passive"))
      (node (ref "U4") (pin "45") (pinfunction "GND_45") (pintype "passive"))
      (node (ref "U4") (pin "5") (pinfunction "GND_5") (pintype "passive"))
      (node (ref "U5") (pin "2") (pinfunction "GND_2") (pintype "passive"))
    )
    (net (code "17") (name "JD_PWR0") (class "Default")
      (node (ref "D12") (pin "1") (pinfunction "K_1") (pintype "passive"))
      (node (ref "D2") (pin "1") (pinfunction "K_1") (pintype "passive"))
      (node (ref "J6") (pin "3") (pinfunction "P_3") (pintype "passive"))
      (node (ref "MH1") (pin "1") (pinfunction "1_1") (pintype "passive"))
    )
    (net (code "18") (name "JD_PWR1") (class "Default")
      (node (ref "D1") (pin "1") (pinfunction "K_1") (pintype "passive"))
      (node (ref "D13") (pin "1") (pinfunction "K_1") (pintype "passive"))
      (node (ref "J4") (pin "3") (pinfunction "P_3") (pintype "passive"))
    )
    (net (code "19") (name "JD_PWR2") (class "Default")
      (node (ref "D14") (pin "1") (pinfunction "K_1") (pintype "passive"))
      (node (ref "D4") (pin "1") (pinfunction "K_1") (pintype "passive"))
      (node (ref "J3") (pin "3") (pinfunction "P_3") (pintype "passive"))
    )
    (net (code "20") (name "Net-(C6-Pad2)") (class "Default")
      (node (ref "C6") (pin "2") (pinfunction "2_2") (pintype "passive"))
      (node (ref "FB1") (pin "2") (pinfunction "2_2") (pintype "passive"))
      (node (ref "R14") (pin "2") (pinfunction "2_2") (pintype "passive"))
    )
    (net (code "21") (name "Net-(D1-A)") (class "Default")
      (node (ref "C8") (pin "2") (pinfunction "2_2") (pintype "passive"))
      (node (ref "D1") (pin "2") (pinfunction "A_2") (pintype "passive"))
      (node (ref "U3") (pin "6") (pinfunction "OUT_6") (pintype "passive"))
    )
    (net (code "22") (name "Net-(D2-A)") (class "Default")
      (node (ref "C3") (pin "2") (pinfunction "2_2") (pintype "passive"))
      (node (ref "D2") (pin "2") (pinfunction "A_2") (pintype "passive"))
      (node (ref "U2") (pin "6") (pinfunction "OUT_6") (pintype "passive"))
    )
    (net (code "23") (name "Net-(D4-A)") (class "Default")
      (node (ref "C13") (pin "2") (pinfunction "2_2") (pintype "passive"))
      (node (ref "D4") (pin "2") (pinfunction "A_2") (pintype "passive"))
      (node (ref "U5") (pin "6") (pinfunction "OUT_6") (pintype "passive"))
    )
    (net (code "24") (name "Net-(D6-K)") (class "Default")
      (node (ref "D6") (pin "1") (pinfunction "K_1") (pintype "passive"))
      (node (ref "R13") (pin "2") (pinfunction "2_2") (pintype "passive"))
    )
    (net (code "25") (name "Net-(D11-DIN)") (class "Default")
      (node (ref "D11") (pin "3") (pinfunction "DIN_3") (pintype "passive"))
      (node (ref "D3") (pin "1") (pinfunction "DOUT_1") (pintype "passive"))
    )
    (net (code "26") (name "Net-(D11-DOUT)") (class "Default")
      (node (ref "D11") (pin "1") (pinfunction "DOUT_1") (pintype "passive"))
      (node (ref "D15") (pin "3") (pinfunction "DIN_3") (pintype "passive"))
    )
    (net (code "27") (name "Net-(D15-DOUT)") (class "Default")
      (node (ref "D15") (pin "1") (pinfunction "DOUT_1") (pintype "passive"))
      (node (ref "D16") (pin "3") (pinfunction "DIN_3") (pintype "passive"))
    )
    (net (code "28") (name "Net-(U2-ILIM)") (class "Default")
      (node (ref "R2") (pin "2") (pinfunction "2_2") (pintype "passive"))
      (node (ref "U2") (pin "5") (pinfunction "ILIM_5") (pintype "passive"))
    )
    (net (code "29") (name "Net-(U3-ILIM)") (class "Default")
      (node (ref "R7") (pin "2") (pinfunction "2_2") (pintype "passive"))
      (node (ref "U3") (pin "5") (pinfunction "ILIM_5") (pintype "passive"))
    )
    (net (code "30") (name "Net-(U4-P0_1)") (class "Default")
      (node (ref "TP2") (pin "1") (pinfunction "1_1") (pintype "passive"))
      (node (ref "U4") (pin "17") (pinfunction "P0_1_17") (pintype "passive"))
    )
    (net (code "31") (name "Net-(U4-P0_3)") (class "Default")
      (node (ref "TP3") (pin "1") (pinfunction "1_1") (pintype "passive"))
      (node (ref "U4") (pin "20") (pinfunction "P0_3_20") (pintype "passive"))
    )
    (net (code "32") (name "Net-(U4-P0_4)") (class "Default")
      (node (ref "TP4") (pin "1") (pinfunction "1_1") (pintype "passive"))
      (node (ref "U4") (pin "21") (pinfunction "P0_4_21") (pintype "passive"))
    )
    (net (code "33") (name "Net-(U4-P0_5)") (class "Default")
      (node (ref "TP5") (pin "1") (pinfunction "1_1") (pintype "passive"))
      (node (ref "U4") (pin "23") (pinfunction "P0_5_23") (pintype "passive"))
    )
    (net (code "34") (name "Net-(U4-P0_6)") (class "Default")
      (node (ref "TP6") (pin "1") (pinfunction "1_1") (pintype "passive"))
      (node (ref "U4") (pin "25") (pinfunction "P0_6_25") (pintype "passive"))
    )
    (net (code "35") (name "Net-(U5-ILIM)") (class "Default")
      (node (ref "R8") (pin "2") (pinfunction "2_2") (pintype "passive"))
      (node (ref "U5") (pin "5") (pinfunction "ILIM_5") (pintype "passive"))
    )
    (net (code "36") (name "VUSB") (class "Default")
      (node (ref "C1") (pin "2") (pinfunction "2_2") (pintype "passive"))
      (node (ref "C10") (pin "2") (pinfunction "2_2") (pintype "passive"))
      (node (ref "C11") (pin "2") (pinfunction "2_2") (pintype "passive"))
      (node (ref "C12") (pin "2") (pinfunction "2_2") (pintype "passive"))
      (node (ref "C14") (pin "2") (pinfunction "2_2") (pintype "passive"))
      (node (ref "C15") (pin "2") (pinfunction "2_2") (pintype "passive"))
      (node (ref "C4") (pin "2") (pinfunction "2_2") (pintype "passive"))
      (node (ref "C9") (pin "2") (pinfunction "2_2") (pintype "passive"))
      (node (ref "D11") (pin "4") (pinfunction "VDD_4") (pintype "passive"))
      (node (ref "D15") (pin "4") (pinfunction "VDD_4") (pintype "passive"))
      (node (ref "D16") (pin "4") (pinfunction "VDD_4") (pintype "passive"))
      (node (ref "D3") (pin "4") (pinfunction "VDD_4") (pintype "passive"))
      (node (ref "D5") (pin "4") (pinfunction "VCC_4") (pintype "power_in"))
      (node (ref "J2") (pin "A4") (pinfunction "VBUS_A4") (pintype "passive"))
      (node (ref "J2") (pin "A9") (pinfunction "VBUS_A9") (pintype "passive"))
      (node (ref "J2") (pin "B4") (pinfunction "VBUS_B4") (pintype "passive"))
      (node (ref "J2") (pin "B9") (pinfunction "VBUS_B9") (pintype "passive"))
      (node (ref "R1") (pin "1") (pinfunction "1_1") (pintype "passive"))
      (node (ref "R5") (pin "1") (pinfunction "1_1") (pintype "passive"))
      (node (ref "R6") (pin "1") (pinfunction "1_1") (pintype "passive"))
      (node (ref "U1") (pin "1") (pinfunction "IN_1") (pintype "passive"))
      (node (ref "U1") (pin "3") (pinfunction "EN_3") (pintype "passive"))
      (node (ref "U2") (pin "1") (pinfunction "IN_1") (pintype "passive"))
      (node (ref "U3") (pin "1") (pinfunction "IN_1") (pintype "passive"))
      (node (ref "U4") (pin "58") (pinfunction "VBUS_58") (pintype "passive"))
      (node (ref "U5") (pin "1") (pinfunction "IN_1") (pintype "passive"))
    )
    (net (code "37") (name "unconnected-(D16-DOUT-Pad1)") (class "Default")
      (node (ref "D16") (pin "1") (pinfunction "DOUT_1") (pintype "passive+no_connect"))
    )
    (net (code "38") (name "unconnected-(J2-SBU1-PadA8)") (class "Default")
      (node (ref "J2") (pin "A8") (pinfunction "SBU1_A8") (pintype "passive+no_connect"))
    )
    (net (code "39") (name "unconnected-(J2-SBU2-PadB8)") (class "Default")
      (node (ref "J2") (pin "B8") (pinfunction "SBU2_B8") (pintype "passive+no_connect"))
    )
    (net (code "40") (name "unconnected-(SW1-A-Pad3)") (class "Default")
      (node (ref "SW1") (pin "3") (pinfunction "A_3") (pintype "passive+no_connect"))
    )
    (net (code "41") (name "unconnected-(SW1-B-Pad4)") (class "Default")
      (node (ref "SW1") (pin "4") (pinfunction "B_4") (pintype "passive+no_connect"))
    )
    (net (code "42") (name "unconnected-(U4-P0_2-Pad22)") (class "Default")
      (node (ref "U4") (pin "22") (pinfunction "P0_2_22") (pintype "passive+no_connect"))
    )
    (net (code "43") (name "unconnected-(U4-P0_8-Pad27)") (class "Default")
      (node (ref "U4") (pin "27") (pinfunction "P0_8_27") (pintype "passive+no_connect"))
    )
    (net (code "44") (name "unconnected-(U4-P0_9-Pad26)") (class "Default")
      (node (ref "U4") (pin "26") (pinfunction "P0_9_26") (pintype "passive+no_connect"))
    )
    (net (code "45") (name "unconnected-(U4-P0_10-Pad29)") (class "Default")
      (node (ref "U4") (pin "29") (pinfunction "P0_10_29") (pintype "passive+no_connect"))
    )
    (net (code "46") (name "unconnected-(U4-P0_11-Pad34)") (class "Default")
      (node (ref "U4") (pin "34") (pinfunction "P0_11_34") (pintype "passive+no_connect"))
    )
    (net (code "47") (name "unconnected-(U4-P0_12-Pad64)") (class "Default")
      (node (ref "U4") (pin "64") (pinfunction "P0_12_64") (pintype "passive+no_connect"))
    )
    (net (code "48") (name "unconnected-(U4-P0_13-Pad41)") (class "Default")
      (node (ref "U4") (pin "41") (pinfunction "P0_13_41") (pintype "passive+no_connect"))
    )
    (net (code "49") (name "unconnected-(U4-P0_15-Pad35)") (class "Default")
      (node (ref "U4") (pin "35") (pinfunction "P0_15_35") (pintype "passive+no_connect"))
    )
    (net (code "50") (name "unconnected-(U4-P0_16-Pad36)") (class "Default")
      (node (ref "U4") (pin "36") (pinfunction "P0_16_36") (pintype "passive+no_connect"))
    )
    (net (code "51") (name "unconnected-(U4-P0_17-Pad37)") (class "Default")
      (node (ref "U4") (pin "37") (pinfunction "P0_17_37") (pintype "passive+no_connect"))
    )
    (net (code "52") (name "unconnected-(U4-P0_19-Pad48)") (class "Default")
      (node (ref "U4") (pin "48") (pinfunction "P0_19_48") (pintype "passive+no_connect"))
    )
    (net (code "53") (name "unconnected-(U4-P0_20-Pad62)") (class "Default")
      (node (ref "U4") (pin "62") (pinfunction "P0_20_62") (pintype "passive+no_connect"))
    )
    (net (code "54") (name "unconnected-(U4-P0_21-Pad60)") (class "Default")
      (node (ref "U4") (pin "60") (pinfunction "P0_21_60") (pintype "passive+no_connect"))
    )
    (net (code "55") (name "unconnected-(U4-P0_22-Pad44)") (class "Default")
      (node (ref "U4") (pin "44") (pinfunction "P0_22_44") (pintype "passive+no_connect"))
    )
    (net (code "56") (name "unconnected-(U4-P0_23-Pad53)") (class "Default")
      (node (ref "U4") (pin "53") (pinfunction "P0_23_53") (pintype "passive+no_connect"))
    )
    (net (code "57") (name "unconnected-(U4-P0_27-Pad8)") (class "Default")
      (node (ref "U4") (pin "8") (pinfunction "P0_27_8") (pintype "passive+no_connect"))
    )
    (net (code "58") (name "unconnected-(U4-P0_28-Pad9)") (class "Default")
      (node (ref "U4") (pin "9") (pinfunction "P0_28_9") (pintype "passive+no_connect"))
    )
    (net (code "59") (name "unconnected-(U4-P0_29-Pad10)") (class "Default")
      (node (ref "U4") (pin "10") (pinfunction "P0_29_10") (pintype "passive+no_connect"))
    )
    (net (code "60") (name "unconnected-(U4-P1_0-Pad38)") (class "Default")
      (node (ref "U4") (pin "38") (pinfunction "P1_0_38") (pintype "passive+no_connect"))
    )
    (net (code "61") (name "unconnected-(U4-P1_1-Pad31)") (class "Default")
      (node (ref "U4") (pin "31") (pinfunction "P1_1_31") (pintype "passive+no_connect"))
    )
    (net (code "62") (name "unconnected-(U4-P1_2-Pad32)") (class "Default")
      (node (ref "U4") (pin "32") (pinfunction "P1_2_32") (pintype "passive+no_connect"))
    )
    (net (code "63") (name "unconnected-(U4-P1_3-Pad49)") (class "Default")
      (node (ref "U4") (pin "49") (pinfunction "P1_3_49") (pintype "passive+no_connect"))
    )
    (net (code "64") (name "unconnected-(U4-P1_4-Pad61)") (class "Default")
      (node (ref "U4") (pin "61") (pinfunction "P1_4_61") (pintype "passive+no_connect"))
    )
    (net (code "65") (name "unconnected-(U4-P1_5-Pad51)") (class "Default")
      (node (ref "U4") (pin "51") (pinfunction "P1_5_51") (pintype "passive+no_connect"))
    )
    (net (code "66") (name "unconnected-(U4-P1_6-Pad65)") (class "Default")
      (node (ref "U4") (pin "65") (pinfunction "P1_6_65") (pintype "passive+no_connect"))
    )
    (net (code "67") (name "unconnected-(U4-P1_7-Pad66)") (class "Default")
      (node (ref "U4") (pin "66") (pinfunction "P1_7_66") (pintype "passive+no_connect"))
    )
    (net (code "68") (name "unconnected-(U4-P1_8-Pad54)") (class "Default")
      (node (ref "U4") (pin "54") (pinfunction "P1_8_54") (pintype "passive+no_connect"))
    )
    (net (code "69") (name "unconnected-(U4-P1_9-Pad52)") (class "Default")
      (node (ref "U4") (pin "52") (pinfunction "P1_9_52") (pintype "passive+no_connect"))
    )
  )
)
